# Prototype.net
KiCad netlist of a schematic drawn in Altium Designer
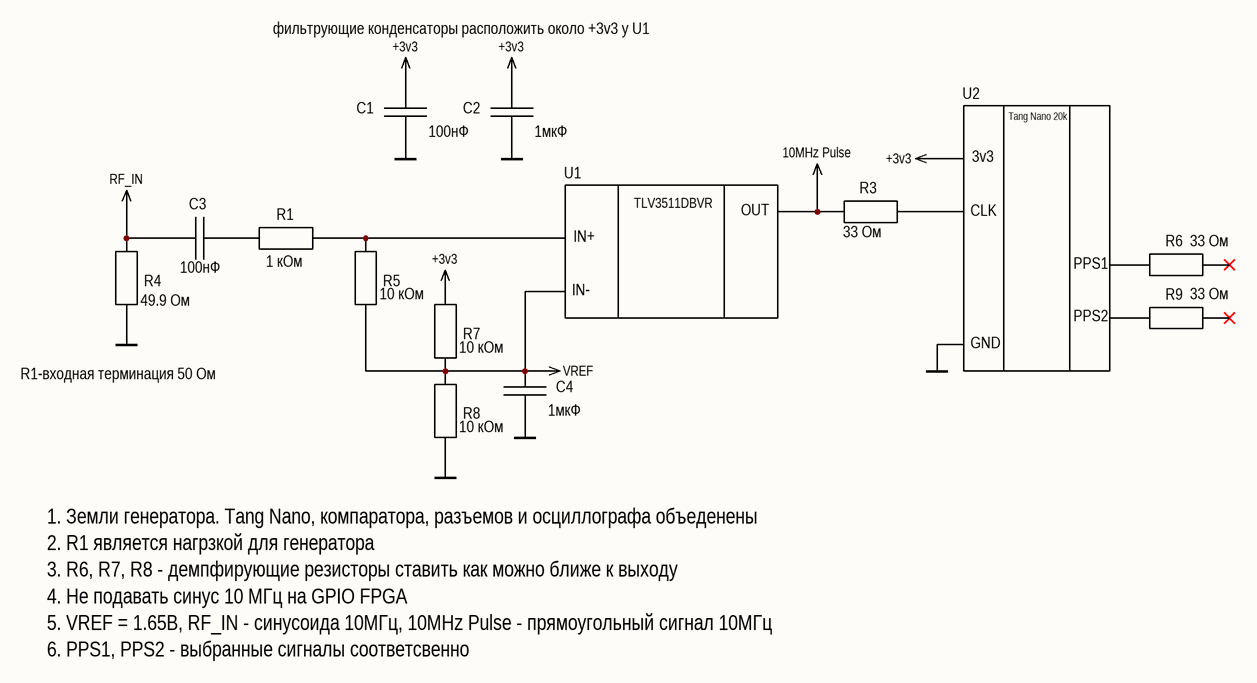
[diagram p0: Prototype.SchDoc]

(export (version "E")
  (design (tool "Eeschema 10.0.6"))
  (components
    (comp (ref "C1")
      (value "100нФ")
      (footprint "C_0805")
      (fields
        (field (name "PART NUMBER") "Конденсатор GRM2165C1H331J (330 пФ +-5% COG 50В)")
        (field (name "TOLERANCE") "±5%")
      )
      (libsource (lib "GOST") (part "C"))
    )
    (comp (ref "C2")
      (value "1мкФ")
      (footprint "C_0805")
      (fields
        (field (name "PART NUMBER") "Конденсатор GRM2165C1H331J (330 пФ +-5% COG 50В)")
        (field (name "TOLERANCE") "±5%")
      )
      (libsource (lib "GOST") (part "C"))
    )
    (comp (ref "C3")
      (value "100нФ")
      (footprint "C_0805")
      (fields
        (field (name "PART NUMBER") "Конденсатор GRM2165C1H331J (330 пФ +-5% COG 50В)")
        (field (name "TOLERANCE") "±5%")
      )
      (libsource (lib "GOST") (part "C"))
    )
    (comp (ref "C4")
      (value "1мкФ")
      (footprint "C_0805")
      (fields
        (field (name "PART NUMBER") "Конденсатор GRM2165C1H331J (330 пФ +-5% COG 50В)")
        (field (name "TOLERANCE") "±5%")
      )
      (libsource (lib "GOST") (part "C"))
    )
    (comp (ref "R1")
      (value "1 кОм")
      (footprint "R_0805")
      (fields
        (field (name "PART NUMBER") "Резистор RC0805FR-071KL (1 кОм +-1%)")
        (field (name "TOLERANCE") "±1%")
        (field (name "POWER") "0.125 W")
      )
      (libsource (lib "GOST") (part "R"))
    )
    (comp (ref "R3")
      (value "33 Ом")
      (footprint "R_0603")
      (description "47Ohm")
      (fields
        (field (name "PART NUMBER") "Резистор RC0603JR-071KL (1 кОм +-5%)")
        (field (name "TOLERANCE") "±5%")
      )
      (libsource (lib "GOST") (part "R"))
    )
    (comp (ref "R4")
      (value "49.9 Ом")
      (footprint "R_0603")
      (description "47Ohm")
      (fields
        (field (name "PART NUMBER") "Резистор RC0603JR-071KL (1 кОм +-5%)")
        (field (name "TOLERANCE") "±5%")
      )
      (libsource (lib "GOST") (part "R"))
    )
    (comp (ref "R5")
      (value "10 кОм")
      (footprint "R_0603")
      (description "47Ohm")
      (fields
        (field (name "PART NUMBER") "Резистор RC0603JR-071KL (1 кОм +-5%)")
        (field (name "TOLERANCE") "±5%")
      )
      (libsource (lib "GOST") (part "R"))
    )
    (comp (ref "R6")
      (value "33 Ом")
      (footprint "R_0603")
      (description "47Ohm")
      (fields
        (field (name "PART NUMBER") "Резистор RC0603JR-071KL (1 кОм +-5%)")
        (field (name "TOLERANCE") "±5%")
      )
      (libsource (lib "GOST") (part "R"))
    )
    (comp (ref "R7")
      (value "10 кОм")
      (footprint "R_0603")
      (description "47Ohm")
      (fields
        (field (name "PART NUMBER") "Резистор RC0603JR-071KL (1 кОм +-5%)")
        (field (name "TOLERANCE") "±5%")
      )
      (libsource (lib "GOST") (part "R"))
    )
    (comp (ref "R8")
      (value "10 кОм")
      (footprint "R_0603")
      (description "47Ohm")
      (fields
        (field (name "PART NUMBER") "Резистор RC0603JR-071KL (1 кОм +-5%)")
        (field (name "TOLERANCE") "±5%")
      )
      (libsource (lib "GOST") (part "R"))
    )
    (comp (ref "R9")
      (value "33 Ом")
      (footprint "R_0603")
      (description "47Ohm")
      (fields
        (field (name "PART NUMBER") "Резистор RC0603JR-071KL (1 кОм +-5%)")
        (field (name "TOLERANCE") "±5%")
      )
      (libsource (lib "GOST") (part "R"))
    )
    (comp (ref "U1") (value "TLV3511DBVR") (libsource (lib "Lib_Prototype") (part "TLV3511DBVR")))
    (comp (ref "U2") (value "Tang Nano 20K") (libsource (lib "Lib_Prototype") (part "Tang Nano 20K")))
  )
  (nets
    (net (code "1") (name "+3v3") (class "Default")
      (node (ref "C1") (pin "2") (pinfunction "2_2") (pintype "passive"))
      (node (ref "C2") (pin "2") (pinfunction "2_2") (pintype "passive"))
      (node (ref "R7") (pin "2") (pinfunction "2_2") (pintype "passive"))
      (node (ref "U2") (pin "2") (pinfunction "2_2") (pintype "passive"))
    )
    (net (code "2") (name "10MHz Pulse") (class "Default")
      (node (ref "R3") (pin "2") (pinfunction "2_2") (pintype "passive"))
      (node (ref "U1") (pin "4") (pinfunction "4_4") (pintype "passive"))
    )
    (net (code "3") (name "GND") (class "Default")
      (node (ref "C1") (pin "1") (pinfunction "1_1") (pintype "passive"))
      (node (ref "C2") (pin "1") (pinfunction "1_1") (pintype "passive"))
      (node (ref "C4") (pin "1") (pinfunction "1_1") (pintype "passive"))
      (node (ref "R4") (pin "1") (pinfunction "1_1") (pintype "passive"))
      (node (ref "R8") (pin "1") (pinfunction "1_1") (pintype "passive"))
      (node (ref "U2") (pin "1") (pinfunction "1_1") (pintype "passive"))
    )
    (net (code "4") (name "Net-(C3-Pad2)") (class "Default")
      (node (ref "C3") (pin "2") (pinfunction "2_2") (pintype "passive"))
      (node (ref "R1") (pin "1") (pinfunction "1_1") (pintype "passive"))
    )
    (net (code "5") (name "Net-(R1-Pad2)") (class "Default")
      (node (ref "R1") (pin "2") (pinfunction "2_2") (pintype "passive"))
      (node (ref "R5") (pin "2") (pinfunction "2_2") (pintype "passive"))
      (node (ref "U1") (pin "2") (pinfunction "2_2") (pintype "passive"))
    )
    (net (code "6") (name "Net-(R3-Pad1)") (class "Default")
      (node (ref "R3") (pin "1") (pinfunction "1_1") (pintype "passive"))
      (node (ref "U2") (pin "3") (pinfunction "3_3") (pintype "passive"))
    )
    (net (code "7") (name "Net-(R6-Pad2)") (class "Default")
      (node (ref "R6") (pin "2") (pinfunction "2_2") (pintype "passive"))
      (node (ref "U2") (pin "4") (pinfunction "4_4") (pintype "passive"))
    )
    (net (code "8") (name "Net-(R9-Pad2)") (class "Default")
      (node (ref "R9") (pin "2") (pinfunction "2_2") (pintype "passive"))
      (node (ref "U2") (pin "5") (pinfunction "5_5") (pintype "passive"))
    )
    (net (code "9") (name "RF_IN") (class "Default")
      (node (ref "C3") (pin "1") (pinfunction "1_1") (pintype "passive"))
      (node (ref "R4") (pin "2") (pinfunction "2_2") (pintype "passive"))
    )
    (net (code "10") (name "VREF") (class "Default")
      (node (ref "C4") (pin "2") (pinfunction "2_2") (pintype "passive"))
      (node (ref "R5") (pin "1") (pinfunction "1_1") (pintype "passive"))
      (node (ref "R7") (pin "1") (pinfunction "1_1") (pintype "passive"))
      (node (ref "R8") (pin "2") (pinfunction "2_2") (pintype "passive"))
      (node (ref "U1") (pin "1") (pinfunction "1_1") (pintype "passive"))
    )
    (net (code "11") (name "unconnected-(R6-Pad1)") (class "Default")
      (node (ref "R6") (pin "1") (pinfunction "1_1") (pintype "passive+no_connect"))
    )
    (net (code "12") (name "unconnected-(R9-Pad1)") (class "Default")
      (node (ref "R9") (pin "1") (pinfunction "1_1") (pintype "passive+no_connect"))
    )
  )
)
